# schema.net
KiCad netlist of a schematic drawn in EasyEDA
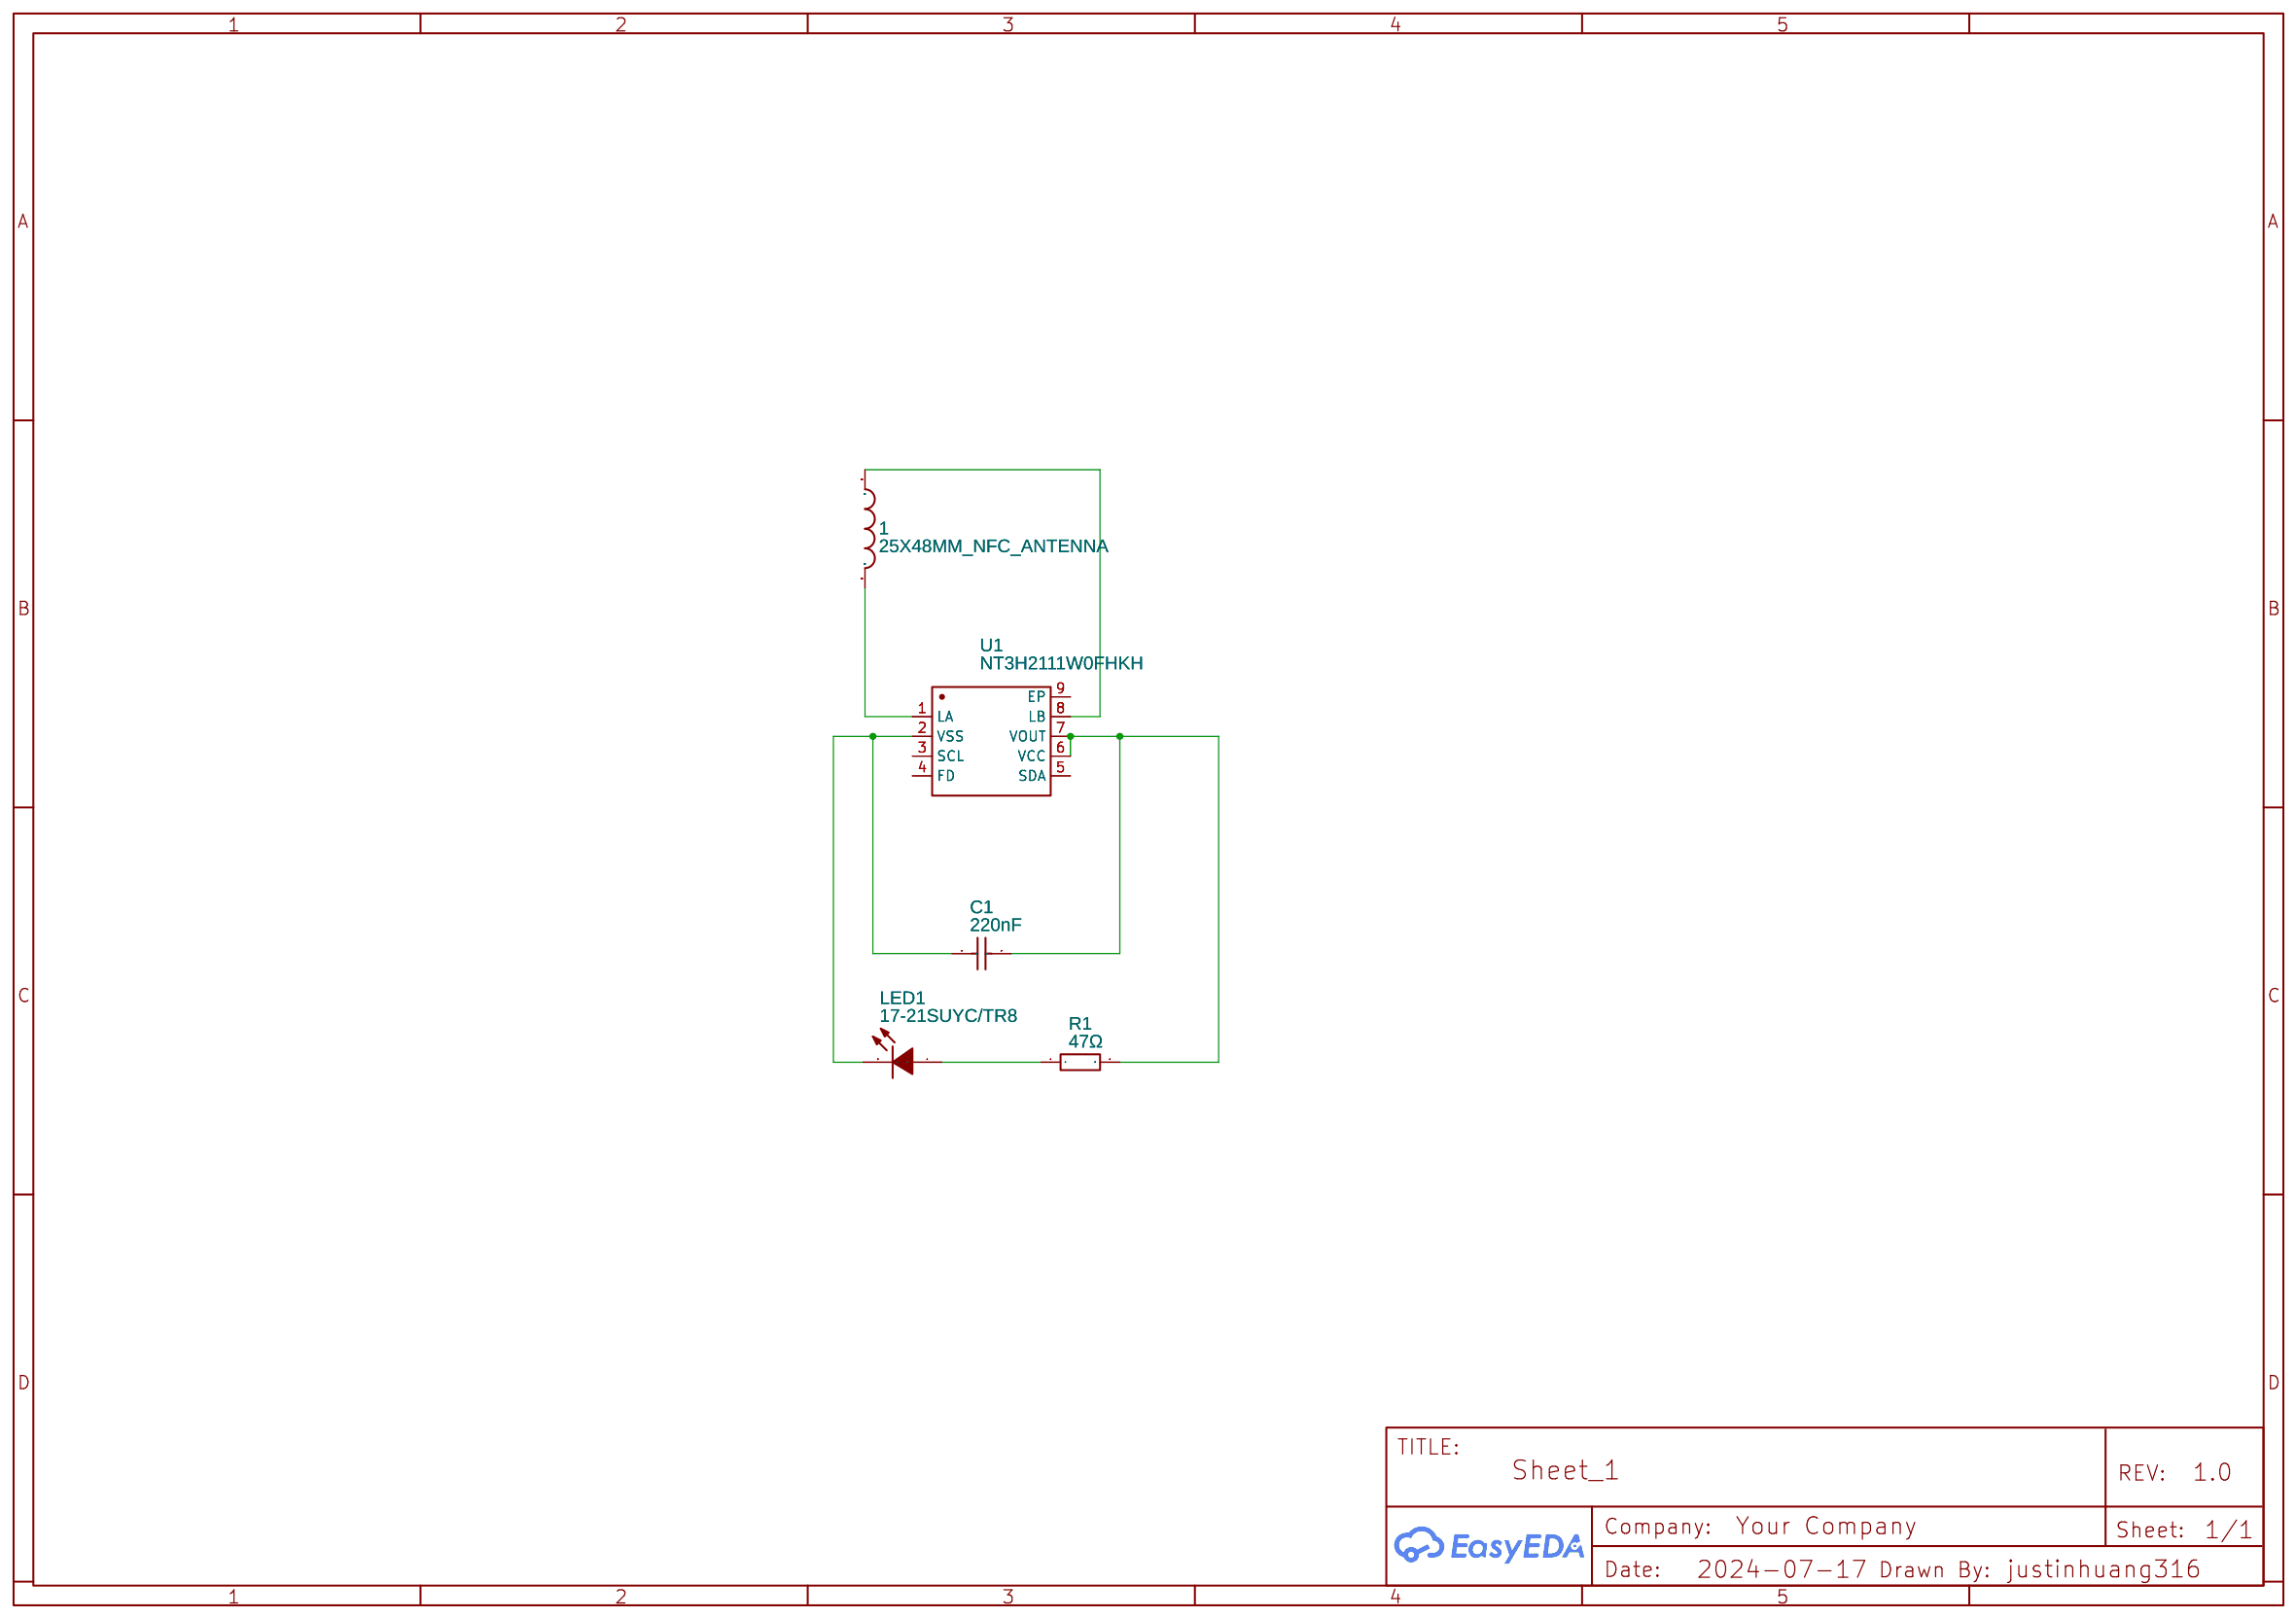
[diagram p0: schematic sheet]

(export (version "E")
  (design (tool "Eeschema 10.0.6"))
  (components
    (comp (ref "1") (value "25X48MM_NFC_ANTENNA") (libsource (lib "") (part "25X48MM_NFC_ANTENNA")))
    (comp (ref "C1")
      (value "220nF")
      (fields
        (field (name "Manufacturer Part") "CL10B224KA8NNNC")
        (field (name "Manufacturer") "SAMSUNG(三星)")
      )
      (libsource (lib "") (part "CL10B224KA8NNNC"))
    )
    (comp (ref "LED1")
      (value "17-21SUYC/TR8")
      (fields (field (name "Manufacturer Part") "KT-0805黄灯") (field (name "Manufacturer") "KENTO"))
      (libsource (lib "") (part "17-21SUYC/TR8"))
    )
    (comp (ref "R1")
      (value "47Ω")
      (fields
        (field (name "Manufacturer Part") "0603WAF470JT5E")
        (field (name "Manufacturer") "UNI-ROYAL(厚声)")
      )
      (libsource (lib "") (part "0603WAF470JT5E"))
    )
    (comp (ref "U1")
      (value "NT3H2111W0FHKH")
      (fields (field (name "Manufacturer") "NXP(恩智浦)"))
      (libsource (lib "") (part "NT3H2111W0FHKH"))
    )
  )
  (nets
    (net (code "1") (name "Net-(LED1-+)") (class "Default")
      (node (ref "LED1") (pin "1") (pinfunction "+_1") (pintype "unspecified"))
      (node (ref "R1") (pin "1") (pinfunction "1_1") (pintype "input"))
    )
    (net (code "2") (name "Net-(LED1--)") (class "Default")
      (node (ref "C1") (pin "1") (pinfunction "1_1") (pintype "input"))
      (node (ref "LED1") (pin "2") (pinfunction "-_2") (pintype "unspecified"))
      (node (ref "U1") (pin "2") (pinfunction "VSS_2") (pintype "unspecified"))
    )
    (net (code "3") (name "Net-(U1-LA)") (class "Default")
      (node (ref "1") (pin "P$2") (pinfunction "P$2_P$2") (pintype "bidirectional"))
      (node (ref "U1") (pin "1") (pinfunction "LA_1") (pintype "unspecified"))
    )
    (net (code "4") (name "Net-(U1-LB)") (class "Default")
      (node (ref "1") (pin "P$1") (pinfunction "P$1_P$1") (pintype "bidirectional"))
      (node (ref "U1") (pin "8") (pinfunction "LB_8") (pintype "unspecified"))
    )
    (net (code "5") (name "Net-(U1-VCC)") (class "Default")
      (node (ref "C1") (pin "2") (pinfunction "2_2") (pintype "input"))
      (node (ref "R1") (pin "2") (pinfunction "2_2") (pintype "input"))
      (node (ref "U1") (pin "6") (pinfunction "VCC_6") (pintype "unspecified"))
      (node (ref "U1") (pin "7") (pinfunction "VOUT_7") (pintype "unspecified"))
    )
    (net (code "6") (name "unconnected-(U1-EP-Pad9)") (class "Default")
      (node (ref "U1") (pin "9") (pinfunction "EP_9") (pintype "unspecified"))
    )
    (net (code "7") (name "unconnected-(U1-FD-Pad4)") (class "Default")
      (node (ref "U1") (pin "4") (pinfunction "FD_4") (pintype "unspecified"))
    )
    (net (code "8") (name "unconnected-(U1-SCL-Pad3)") (class "Default")
      (node (ref "U1") (pin "3") (pinfunction "SCL_3") (pintype "unspecified"))
    )
    (net (code "9") (name "unconnected-(U1-SDA-Pad5)") (class "Default")
      (node (ref "U1") (pin "5") (pinfunction "SDA_5") (pintype "unspecified"))
    )
  )
)
